# mini_mouse.net
KiCad netlist of a schematic drawn in EAGLE
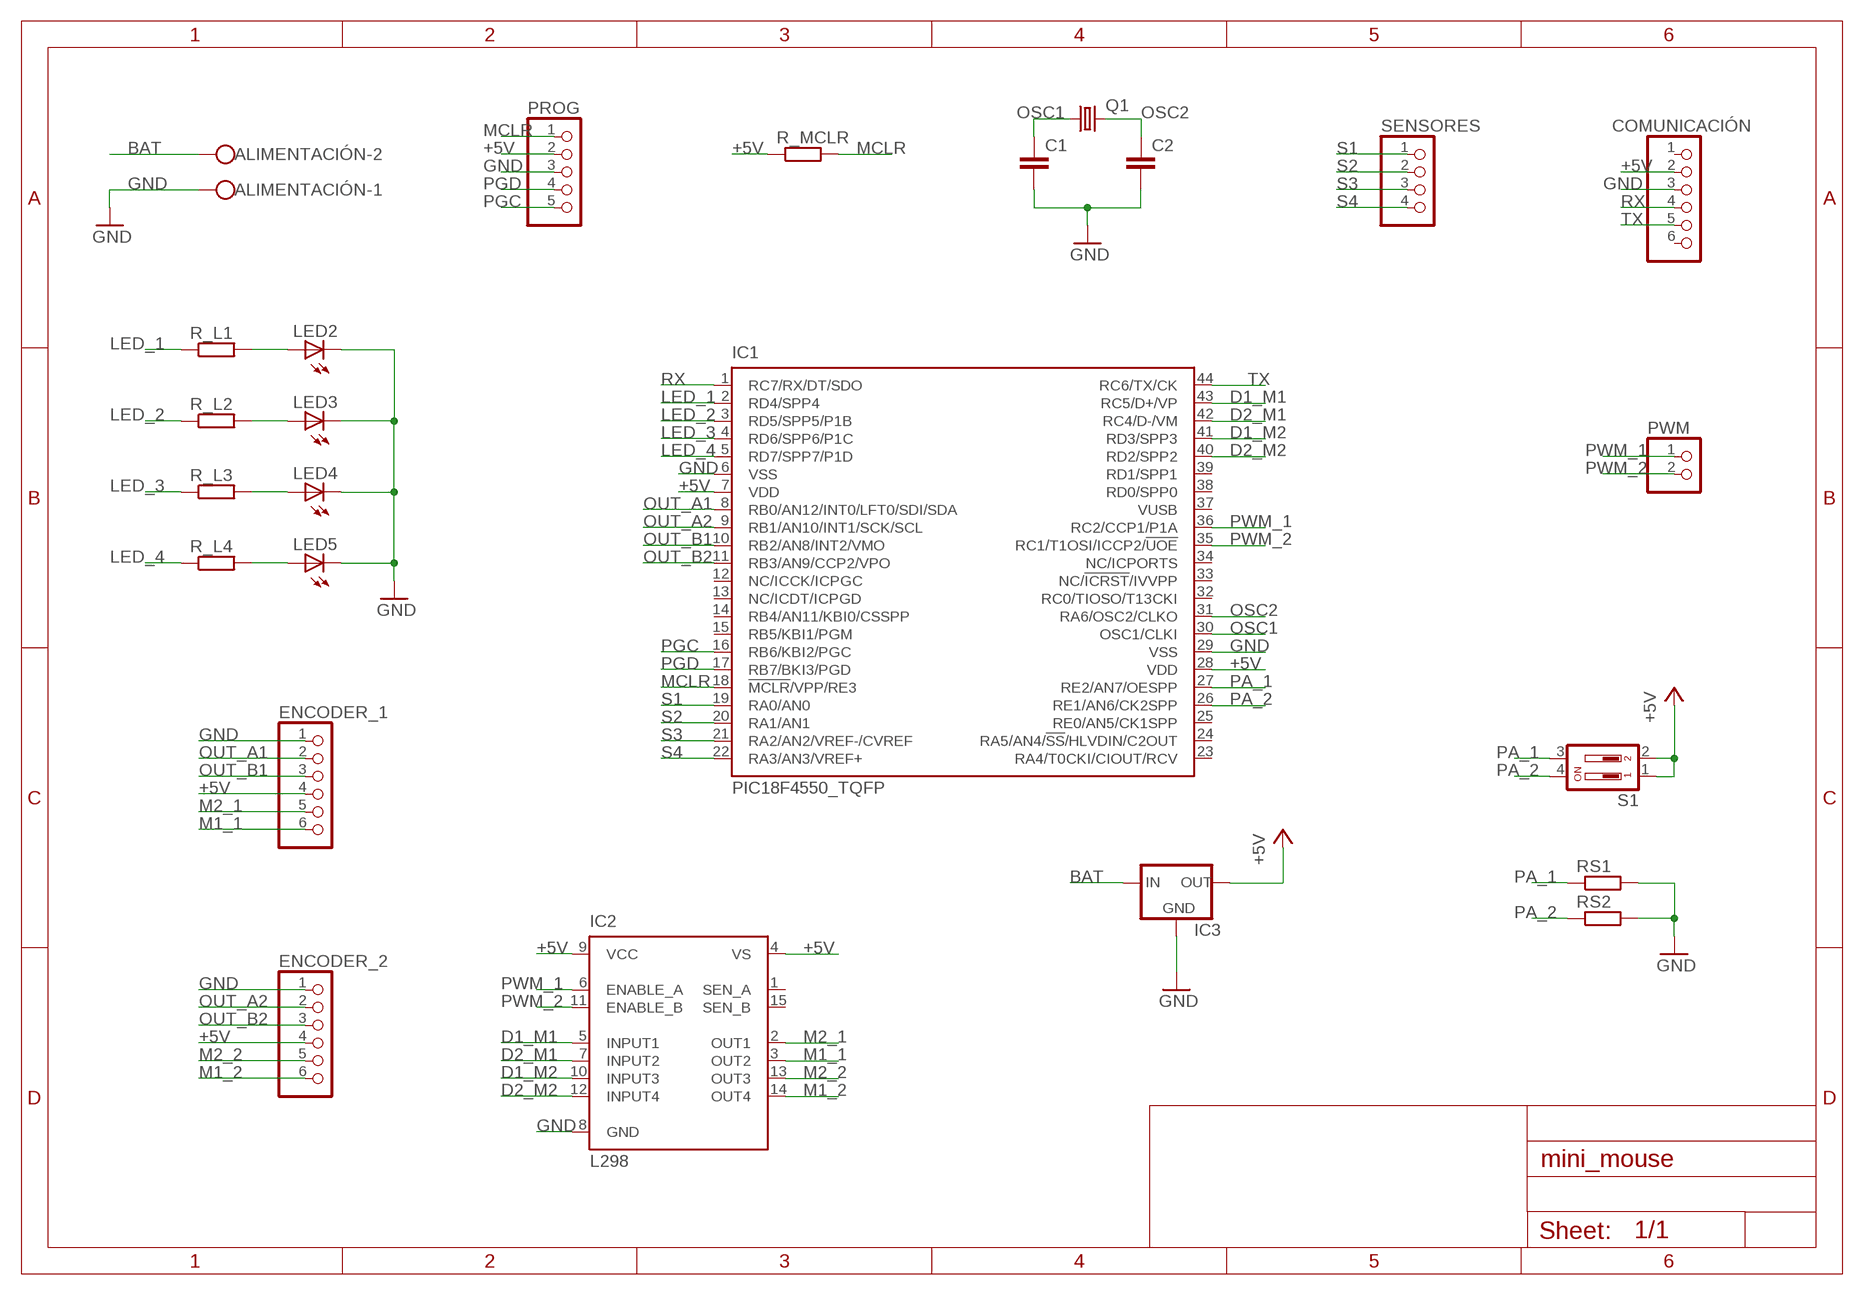
[diagram p0: schematic, sheet 1]

(export (version "E")
  (design (tool "Eeschema 10.0.6"))
  (components
    (comp (ref "ALIMENTACIÓN")
      (value "W237-102")
      (footprint "eagle-import:W237-102")
      (fields (field (name "MPN") "237-102"))
      (libsource (lib "eagle-import") (part "W237-102"))
    )
    (comp (ref "C1")
      (value "C-EUC0603")
      (footprint "eagle-import:C0603")
      (libsource (lib "eagle-import") (part "C-EUC0603"))
    )
    (comp (ref "C2")
      (value "C-EUC0603")
      (footprint "eagle-import:C0603")
      (libsource (lib "eagle-import") (part "C-EUC0603"))
    )
    (comp (ref "COMUNICACIÓN")
      (value "PINHD-1X6")
      (footprint "eagle-import:1X06")
      (libsource (lib "eagle-import") (part "PINHD-1X6"))
    )
    (comp (ref "ENCODER_1")
      (value "PINHD-1X6")
      (footprint "eagle-import:1X06")
      (libsource (lib "eagle-import") (part "PINHD-1X6"))
    )
    (comp (ref "ENCODER_2")
      (value "PINHD-1X6")
      (footprint "eagle-import:1X06")
      (libsource (lib "eagle-import") (part "PINHD-1X6"))
    )
    (comp (ref "IC1")
      (value "PIC18F4550_TQFP")
      (footprint "eagle-import:TQFP44")
      (fields (field (name "MF") "MICROCHIP") (field (name "MPN") "PIC18F4550-I/PT"))
      (libsource (lib "eagle-import") (part "PIC18F4_TQFP550"))
    )
    (comp (ref "IC2")
      (value "L298")
      (footprint "eagle-import:MULTIWATT-15")
      (fields (field (name "MPN") "L298N"))
      (libsource (lib "eagle-import") (part "L298"))
    )
    (comp (ref "IC3")
      (value "78XXL")
      (footprint "eagle-import:78XXL")
      (libsource (lib "eagle-import") (part "78XXL"))
    )
    (comp (ref "LED2")
      (value "LED3MM")
      (footprint "eagle-import:LED3MM")
      (libsource (lib "eagle-import") (part "LED3MM"))
    )
    (comp (ref "LED3")
      (value "LED3MM")
      (footprint "eagle-import:LED3MM")
      (libsource (lib "eagle-import") (part "LED3MM"))
    )
    (comp (ref "LED4")
      (value "LED3MM")
      (footprint "eagle-import:LED3MM")
      (libsource (lib "eagle-import") (part "LED3MM"))
    )
    (comp (ref "LED5")
      (value "LED3MM")
      (footprint "eagle-import:LED3MM")
      (libsource (lib "eagle-import") (part "LED3MM"))
    )
    (comp (ref "PROG")
      (value "PINHD-1X5")
      (footprint "eagle-import:1X05")
      (libsource (lib "eagle-import") (part "PINHD-1X5"))
    )
    (comp (ref "PWM")
      (value "PINHD-1X2")
      (footprint "eagle-import:1X02")
      (libsource (lib "eagle-import") (part "PINHD-1X2"))
    )
    (comp (ref "Q1")
      (value "CRYSTALHC49U-V")
      (footprint "eagle-import:HC49U-V")
      (libsource (lib "eagle-import") (part "CRYSTALHC49U-V"))
    )
    (comp (ref "RS1")
      (value "R-EU_R0603")
      (footprint "eagle-import:R0603")
      (libsource (lib "eagle-import") (part "R-EU_R0603"))
    )
    (comp (ref "RS2")
      (value "R-EU_R0603")
      (footprint "eagle-import:R0603")
      (libsource (lib "eagle-import") (part "R-EU_R0603"))
    )
    (comp (ref "R_L1")
      (value "R-EU_R0603")
      (footprint "eagle-import:R0603")
      (libsource (lib "eagle-import") (part "R-EU_R0603"))
    )
    (comp (ref "R_L2")
      (value "R-EU_R0603")
      (footprint "eagle-import:R0603")
      (libsource (lib "eagle-import") (part "R-EU_R0603"))
    )
    (comp (ref "R_L3")
      (value "R-EU_R0603")
      (footprint "eagle-import:R0603")
      (libsource (lib "eagle-import") (part "R-EU_R0603"))
    )
    (comp (ref "R_L4")
      (value "R-EU_R0603")
      (footprint "eagle-import:R0603")
      (libsource (lib "eagle-import") (part "R-EU_R0603"))
    )
    (comp (ref "R_MCLR")
      (value "R-EU_R0603")
      (footprint "eagle-import:R0603")
      (libsource (lib "eagle-import") (part "R-EU_R0603"))
    )
    (comp (ref "S1")
      (value "DIP02YL")
      (footprint "eagle-import:DIP02YL")
      (libsource (lib "eagle-import") (part "DIP02YL"))
    )
    (comp (ref "SENSORES")
      (value "PINHD-1X4")
      (footprint "eagle-import:1X04")
      (libsource (lib "eagle-import") (part "PINHD-1X4"))
    )
  )
  (nets
    (net (code "1") (name "+5V") (class "Default")
      (node (ref "COMUNICACIÓN") (pin "2") (pinfunction "2_2") (pintype "passive"))
      (node (ref "ENCODER_1") (pin "4") (pinfunction "4_4") (pintype "passive"))
      (node (ref "ENCODER_2") (pin "4") (pinfunction "4_4") (pintype "passive"))
      (node (ref "IC1") (pin "28") (pinfunction "VDD_28") (pintype "power_in"))
      (node (ref "IC1") (pin "7") (pinfunction "VDD_7") (pintype "power_in"))
      (node (ref "IC2") (pin "4") (pinfunction "VS_4") (pintype "power_in"))
      (node (ref "IC2") (pin "9") (pinfunction "VCC_9") (pintype "power_in"))
      (node (ref "IC3") (pin "OUT") (pinfunction "OUT_OUT") (pintype "passive"))
      (node (ref "PROG") (pin "2") (pinfunction "2_2") (pintype "passive"))
      (node (ref "R_MCLR") (pin "1") (pinfunction "1_1") (pintype "passive"))
      (node (ref "S1") (pin "1") (pinfunction "1_1") (pintype "passive"))
      (node (ref "S1") (pin "2") (pinfunction "2_2") (pintype "passive"))
    )
    (net (code "2") (name "/BAT") (class "Default")
      (node (ref "ALIMENTACIÓN") (pin "2") (pinfunction "KL_2") (pintype "passive"))
      (node (ref "IC3") (pin "IN") (pinfunction "IN_IN") (pintype "input"))
    )
    (net (code "3") (name "/D1_M1") (class "Default")
      (node (ref "IC1") (pin "43") (pinfunction "RC5/D+/VP_43") (pintype "bidirectional"))
      (node (ref "IC2") (pin "5") (pinfunction "INPUT1_5") (pintype "input"))
    )
    (net (code "4") (name "/D1_M2") (class "Default")
      (node (ref "IC1") (pin "41") (pinfunction "RD3/SPP3_41") (pintype "bidirectional"))
      (node (ref "IC2") (pin "10") (pinfunction "INPUT3_10") (pintype "input"))
    )
    (net (code "5") (name "/D2_M1") (class "Default")
      (node (ref "IC1") (pin "42") (pinfunction "RC4/D-/VM_42") (pintype "bidirectional"))
      (node (ref "IC2") (pin "7") (pinfunction "INPUT2_7") (pintype "input"))
    )
    (net (code "6") (name "/D2_M2") (class "Default")
      (node (ref "IC1") (pin "40") (pinfunction "RD2/SPP2_40") (pintype "bidirectional"))
      (node (ref "IC2") (pin "12") (pinfunction "INPUT4_12") (pintype "input"))
    )
    (net (code "7") (name "/LED_1") (class "Default")
      (node (ref "IC1") (pin "2") (pinfunction "RD4/SPP4_2") (pintype "bidirectional"))
      (node (ref "R_L1") (pin "1") (pinfunction "1_1") (pintype "passive"))
    )
    (net (code "8") (name "/LED_2") (class "Default")
      (node (ref "IC1") (pin "3") (pinfunction "RD5/SPP5/P1B_3") (pintype "bidirectional"))
      (node (ref "R_L2") (pin "1") (pinfunction "1_1") (pintype "passive"))
    )
    (net (code "9") (name "/LED_3") (class "Default")
      (node (ref "IC1") (pin "4") (pinfunction "RD6/SPP6/P1C_4") (pintype "bidirectional"))
      (node (ref "R_L3") (pin "1") (pinfunction "1_1") (pintype "passive"))
    )
    (net (code "10") (name "/LED_4") (class "Default")
      (node (ref "IC1") (pin "5") (pinfunction "RD7/SPP7/P1D_5") (pintype "bidirectional"))
      (node (ref "R_L4") (pin "1") (pinfunction "1_1") (pintype "passive"))
    )
    (net (code "11") (name "/M1_1") (class "Default")
      (node (ref "ENCODER_1") (pin "6") (pinfunction "6_6") (pintype "passive"))
      (node (ref "IC2") (pin "3") (pinfunction "OUT2_3") (pintype "output"))
    )
    (net (code "12") (name "/M1_2") (class "Default")
      (node (ref "ENCODER_2") (pin "6") (pinfunction "6_6") (pintype "passive"))
      (node (ref "IC2") (pin "14") (pinfunction "OUT4_14") (pintype "output"))
    )
    (net (code "13") (name "/M2_1") (class "Default")
      (node (ref "ENCODER_1") (pin "5") (pinfunction "5_5") (pintype "passive"))
      (node (ref "IC2") (pin "2") (pinfunction "OUT1_2") (pintype "output"))
    )
    (net (code "14") (name "/M2_2") (class "Default")
      (node (ref "ENCODER_2") (pin "5") (pinfunction "5_5") (pintype "passive"))
      (node (ref "IC2") (pin "13") (pinfunction "OUT3_13") (pintype "output"))
    )
    (net (code "15") (name "/MCLR") (class "Default")
      (node (ref "IC1") (pin "18") (pinfunction "~{MCLR}/VPP/RE3_18") (pintype "input"))
      (node (ref "PROG") (pin "1") (pinfunction "1_1") (pintype "passive"))
      (node (ref "R_MCLR") (pin "2") (pinfunction "2_2") (pintype "passive"))
    )
    (net (code "16") (name "/OSC1") (class "Default")
      (node (ref "C1") (pin "1") (pinfunction "1_1") (pintype "passive"))
      (node (ref "IC1") (pin "30") (pinfunction "OSC1/CLKI_30") (pintype "input"))
      (node (ref "Q1") (pin "1") (pinfunction "1_1") (pintype "passive"))
    )
    (net (code "17") (name "/OSC2") (class "Default")
      (node (ref "C2") (pin "1") (pinfunction "1_1") (pintype "passive"))
      (node (ref "IC1") (pin "31") (pinfunction "RA6/OSC2/CLKO_31") (pintype "output"))
      (node (ref "Q1") (pin "2") (pinfunction "2_2") (pintype "passive"))
    )
    (net (code "18") (name "/OUT_A1") (class "Default")
      (node (ref "ENCODER_1") (pin "2") (pinfunction "2_2") (pintype "passive"))
      (node (ref "IC1") (pin "8") (pinfunction "RB0/AN12/INT0/LFT0/SDI/SDA_8") (pintype "bidirectional"))
    )
    (net (code "19") (name "/OUT_A2") (class "Default")
      (node (ref "ENCODER_2") (pin "2") (pinfunction "2_2") (pintype "passive"))
      (node (ref "IC1") (pin "9") (pinfunction "RB1/AN10/INT1/SCK/SCL_9") (pintype "bidirectional"))
    )
    (net (code "20") (name "/OUT_B1") (class "Default")
      (node (ref "ENCODER_1") (pin "3") (pinfunction "3_3") (pintype "passive"))
      (node (ref "IC1") (pin "10") (pinfunction "RB2/AN8/INT2/VMO_10") (pintype "bidirectional"))
    )
    (net (code "21") (name "/OUT_B2") (class "Default")
      (node (ref "ENCODER_2") (pin "3") (pinfunction "3_3") (pintype "passive"))
      (node (ref "IC1") (pin "11") (pinfunction "RB3/AN9/CCP2/VPO_11") (pintype "bidirectional"))
    )
    (net (code "22") (name "/PA_1") (class "Default")
      (node (ref "IC1") (pin "27") (pinfunction "RE2/AN7/OESPP_27") (pintype "bidirectional"))
      (node (ref "RS1") (pin "1") (pinfunction "1_1") (pintype "passive"))
      (node (ref "S1") (pin "3") (pinfunction "3_3") (pintype "passive"))
    )
    (net (code "23") (name "/PA_2") (class "Default")
      (node (ref "IC1") (pin "26") (pinfunction "RE1/AN6/CK2SPP_26") (pintype "bidirectional"))
      (node (ref "RS2") (pin "1") (pinfunction "1_1") (pintype "passive"))
      (node (ref "S1") (pin "4") (pinfunction "4_4") (pintype "passive"))
    )
    (net (code "24") (name "/PGC") (class "Default")
      (node (ref "IC1") (pin "16") (pinfunction "RB6/KBI2/PGC_16") (pintype "bidirectional"))
      (node (ref "PROG") (pin "5") (pinfunction "5_5") (pintype "passive"))
    )
    (net (code "25") (name "/PGD") (class "Default")
      (node (ref "IC1") (pin "17") (pinfunction "RB7/BKI3/PGD_17") (pintype "bidirectional"))
      (node (ref "PROG") (pin "4") (pinfunction "4_4") (pintype "passive"))
    )
    (net (code "26") (name "/PWM_1") (class "Default")
      (node (ref "IC1") (pin "36") (pinfunction "RC2/CCP1/P1A_36") (pintype "bidirectional"))
      (node (ref "IC2") (pin "6") (pinfunction "ENABLE_A_6") (pintype "input"))
      (node (ref "PWM") (pin "1") (pinfunction "1_1") (pintype "passive"))
    )
    (net (code "27") (name "/PWM_2") (class "Default")
      (node (ref "IC1") (pin "35") (pinfunction "RC1/T1OSI/ICCP2/~{UOE}_35") (pintype "bidirectional"))
      (node (ref "IC2") (pin "11") (pinfunction "ENABLE_B_11") (pintype "input"))
      (node (ref "PWM") (pin "2") (pinfunction "2_2") (pintype "passive"))
    )
    (net (code "28") (name "/RX") (class "Default")
      (node (ref "COMUNICACIÓN") (pin "4") (pinfunction "4_4") (pintype "passive"))
      (node (ref "IC1") (pin "1") (pinfunction "RC7/RX/DT/SDO_1") (pintype "bidirectional"))
    )
    (net (code "29") (name "/S1") (class "Default")
      (node (ref "IC1") (pin "19") (pinfunction "RA0/AN0_19") (pintype "bidirectional"))
      (node (ref "SENSORES") (pin "1") (pinfunction "1_1") (pintype "passive"))
    )
    (net (code "30") (name "/S2") (class "Default")
      (node (ref "IC1") (pin "20") (pinfunction "RA1/AN1_20") (pintype "bidirectional"))
      (node (ref "SENSORES") (pin "2") (pinfunction "2_2") (pintype "passive"))
    )
    (net (code "31") (name "/S3") (class "Default")
      (node (ref "IC1") (pin "21") (pinfunction "RA2/AN2/VREF-/CVREF_21") (pintype "bidirectional"))
      (node (ref "SENSORES") (pin "3") (pinfunction "3_3") (pintype "passive"))
    )
    (net (code "32") (name "/S4") (class "Default")
      (node (ref "IC1") (pin "22") (pinfunction "RA3/AN3/VREF+_22") (pintype "bidirectional"))
      (node (ref "SENSORES") (pin "4") (pinfunction "4_4") (pintype "passive"))
    )
    (net (code "33") (name "/TX") (class "Default")
      (node (ref "COMUNICACIÓN") (pin "5") (pinfunction "5_5") (pintype "passive"))
      (node (ref "IC1") (pin "44") (pinfunction "RC6/TX/CK_44") (pintype "bidirectional"))
    )
    (net (code "34") (name "GND") (class "Default")
      (node (ref "ALIMENTACIÓN") (pin "1") (pinfunction "KL_1") (pintype "passive"))
      (node (ref "C1") (pin "2") (pinfunction "2_2") (pintype "passive"))
      (node (ref "C2") (pin "2") (pinfunction "2_2") (pintype "passive"))
      (node (ref "COMUNICACIÓN") (pin "3") (pinfunction "3_3") (pintype "passive"))
      (node (ref "ENCODER_1") (pin "1") (pinfunction "1_1") (pintype "passive"))
      (node (ref "ENCODER_2") (pin "1") (pinfunction "1_1") (pintype "passive"))
      (node (ref "IC1") (pin "29") (pinfunction "VSS_29") (pintype "power_in"))
      (node (ref "IC1") (pin "6") (pinfunction "VSS_6") (pintype "power_in"))
      (node (ref "IC2") (pin "8") (pinfunction "GND_8") (pintype "power_in"))
      (node (ref "IC3") (pin "GND") (pinfunction "GND_GND") (pintype "input"))
      (node (ref "LED2") (pin "K") (pinfunction "C_K") (pintype "passive"))
      (node (ref "LED3") (pin "K") (pinfunction "C_K") (pintype "passive"))
      (node (ref "LED4") (pin "K") (pinfunction "C_K") (pintype "passive"))
      (node (ref "LED5") (pin "K") (pinfunction "C_K") (pintype "passive"))
      (node (ref "PROG") (pin "3") (pinfunction "3_3") (pintype "passive"))
      (node (ref "RS1") (pin "2") (pinfunction "2_2") (pintype "passive"))
      (node (ref "RS2") (pin "2") (pinfunction "2_2") (pintype "passive"))
    )
    (net (code "35") (name "Net-(LED2-PadA)") (class "Default")
      (node (ref "LED2") (pin "A") (pinfunction "A_A") (pintype "passive"))
      (node (ref "R_L1") (pin "2") (pinfunction "2_2") (pintype "passive"))
    )
    (net (code "36") (name "Net-(LED3-PadA)") (class "Default")
      (node (ref "LED3") (pin "A") (pinfunction "A_A") (pintype "passive"))
      (node (ref "R_L2") (pin "2") (pinfunction "2_2") (pintype "passive"))
    )
    (net (code "37") (name "Net-(LED4-PadA)") (class "Default")
      (node (ref "LED4") (pin "A") (pinfunction "A_A") (pintype "passive"))
      (node (ref "R_L3") (pin "2") (pinfunction "2_2") (pintype "passive"))
    )
    (net (code "38") (name "Net-(LED5-PadA)") (class "Default")
      (node (ref "LED5") (pin "A") (pinfunction "A_A") (pintype "passive"))
      (node (ref "R_L4") (pin "2") (pinfunction "2_2") (pintype "passive"))
    )
    (net (code "39") (name "unconnected-(COMUNICACIÓN-Pad1)") (class "Default")
      (node (ref "COMUNICACIÓN") (pin "1") (pinfunction "1_1") (pintype "passive"))
    )
    (net (code "40") (name "unconnected-(COMUNICACIÓN-Pad6)") (class "Default")
      (node (ref "COMUNICACIÓN") (pin "6") (pinfunction "6_6") (pintype "passive"))
    )
    (net (code "41") (name "unconnected-(IC1-NC{slash}ICCK{slash}ICPGC-Pad12)") (class "Default")
      (node (ref "IC1") (pin "12") (pinfunction "NC/ICCK/ICPGC_12") (pintype "bidirectional"))
    )
    (net (code "42") (name "unconnected-(IC1-NC{slash}ICDT{slash}ICPGD-Pad13)") (class "Default")
      (node (ref "IC1") (pin "13") (pinfunction "NC/ICDT/ICPGD_13") (pintype "bidirectional"))
    )
    (net (code "43") (name "unconnected-(IC1-NC{slash}ICPORTS-Pad34)") (class "Default")
      (node (ref "IC1") (pin "34") (pinfunction "NC/ICPORTS_34") (pintype "input"))
    )
    (net (code "44") (name "unconnected-(IC1-NC{slash}~{ICRST}{slash}IVVPP-Pad33)") (class "Default")
      (node (ref "IC1") (pin "33") (pinfunction "NC/~{ICRST}/IVVPP_33") (pintype "input"))
    )
    (net (code "45") (name "unconnected-(IC1-RA4{slash}T0CKI{slash}CIOUT{slash}RCV-Pad23)") (class "Default")
      (node (ref "IC1") (pin "23") (pinfunction "RA4/T0CKI/CIOUT/RCV_23") (pintype "bidirectional"))
    )
    (net (code "46") (name "unconnected-(IC1-RA5{slash}AN4{slash}~{SS}{slash}HLVDIN{slash}C2OUT-Pad24)") (class "Default")
      (node (ref "IC1") (pin "24") (pinfunction "RA5/AN4/~{SS}/HLVDIN/C2OUT_24") (pintype "bidirectional"))
    )
    (net (code "47") (name "unconnected-(IC1-RB4{slash}AN11{slash}KBI0{slash}CSSPP-Pad14)") (class "Default")
      (node (ref "IC1") (pin "14") (pinfunction "RB4/AN11/KBI0/CSSPP_14") (pintype "bidirectional"))
    )
    (net (code "48") (name "unconnected-(IC1-RB5{slash}KBI1{slash}PGM-Pad15)") (class "Default")
      (node (ref "IC1") (pin "15") (pinfunction "RB5/KBI1/PGM_15") (pintype "bidirectional"))
    )
    (net (code "49") (name "unconnected-(IC1-RC0{slash}TIOSO{slash}T13CKI-Pad32)") (class "Default")
      (node (ref "IC1") (pin "32") (pinfunction "RC0/TIOSO/T13CKI_32") (pintype "bidirectional"))
    )
    (net (code "50") (name "unconnected-(IC1-RD0{slash}SPP0-Pad38)") (class "Default")
      (node (ref "IC1") (pin "38") (pinfunction "RD0/SPP0_38") (pintype "bidirectional"))
    )
    (net (code "51") (name "unconnected-(IC1-RD1{slash}SPP1-Pad39)") (class "Default")
      (node (ref "IC1") (pin "39") (pinfunction "RD1/SPP1_39") (pintype "bidirectional"))
    )
    (net (code "52") (name "unconnected-(IC1-RE0{slash}AN5{slash}CK1SPP-Pad25)") (class "Default")
      (node (ref "IC1") (pin "25") (pinfunction "RE0/AN5/CK1SPP_25") (pintype "bidirectional"))
    )
    (net (code "53") (name "unconnected-(IC1-VUSB-Pad37)") (class "Default")
      (node (ref "IC1") (pin "37") (pinfunction "VUSB_37") (pintype "bidirectional"))
    )
    (net (code "54") (name "unconnected-(IC2-SEN_A-Pad1)") (class "Default")
      (node (ref "IC2") (pin "1") (pinfunction "SEN_A_1") (pintype "input"))
    )
    (net (code "55") (name "unconnected-(IC2-SEN_B-Pad15)") (class "Default")
      (node (ref "IC2") (pin "15") (pinfunction "SEN_B_15") (pintype "input"))
    )
  )
)
